# Enabled-Controller.net
KiCad netlist of a schematic drawn in EAGLE
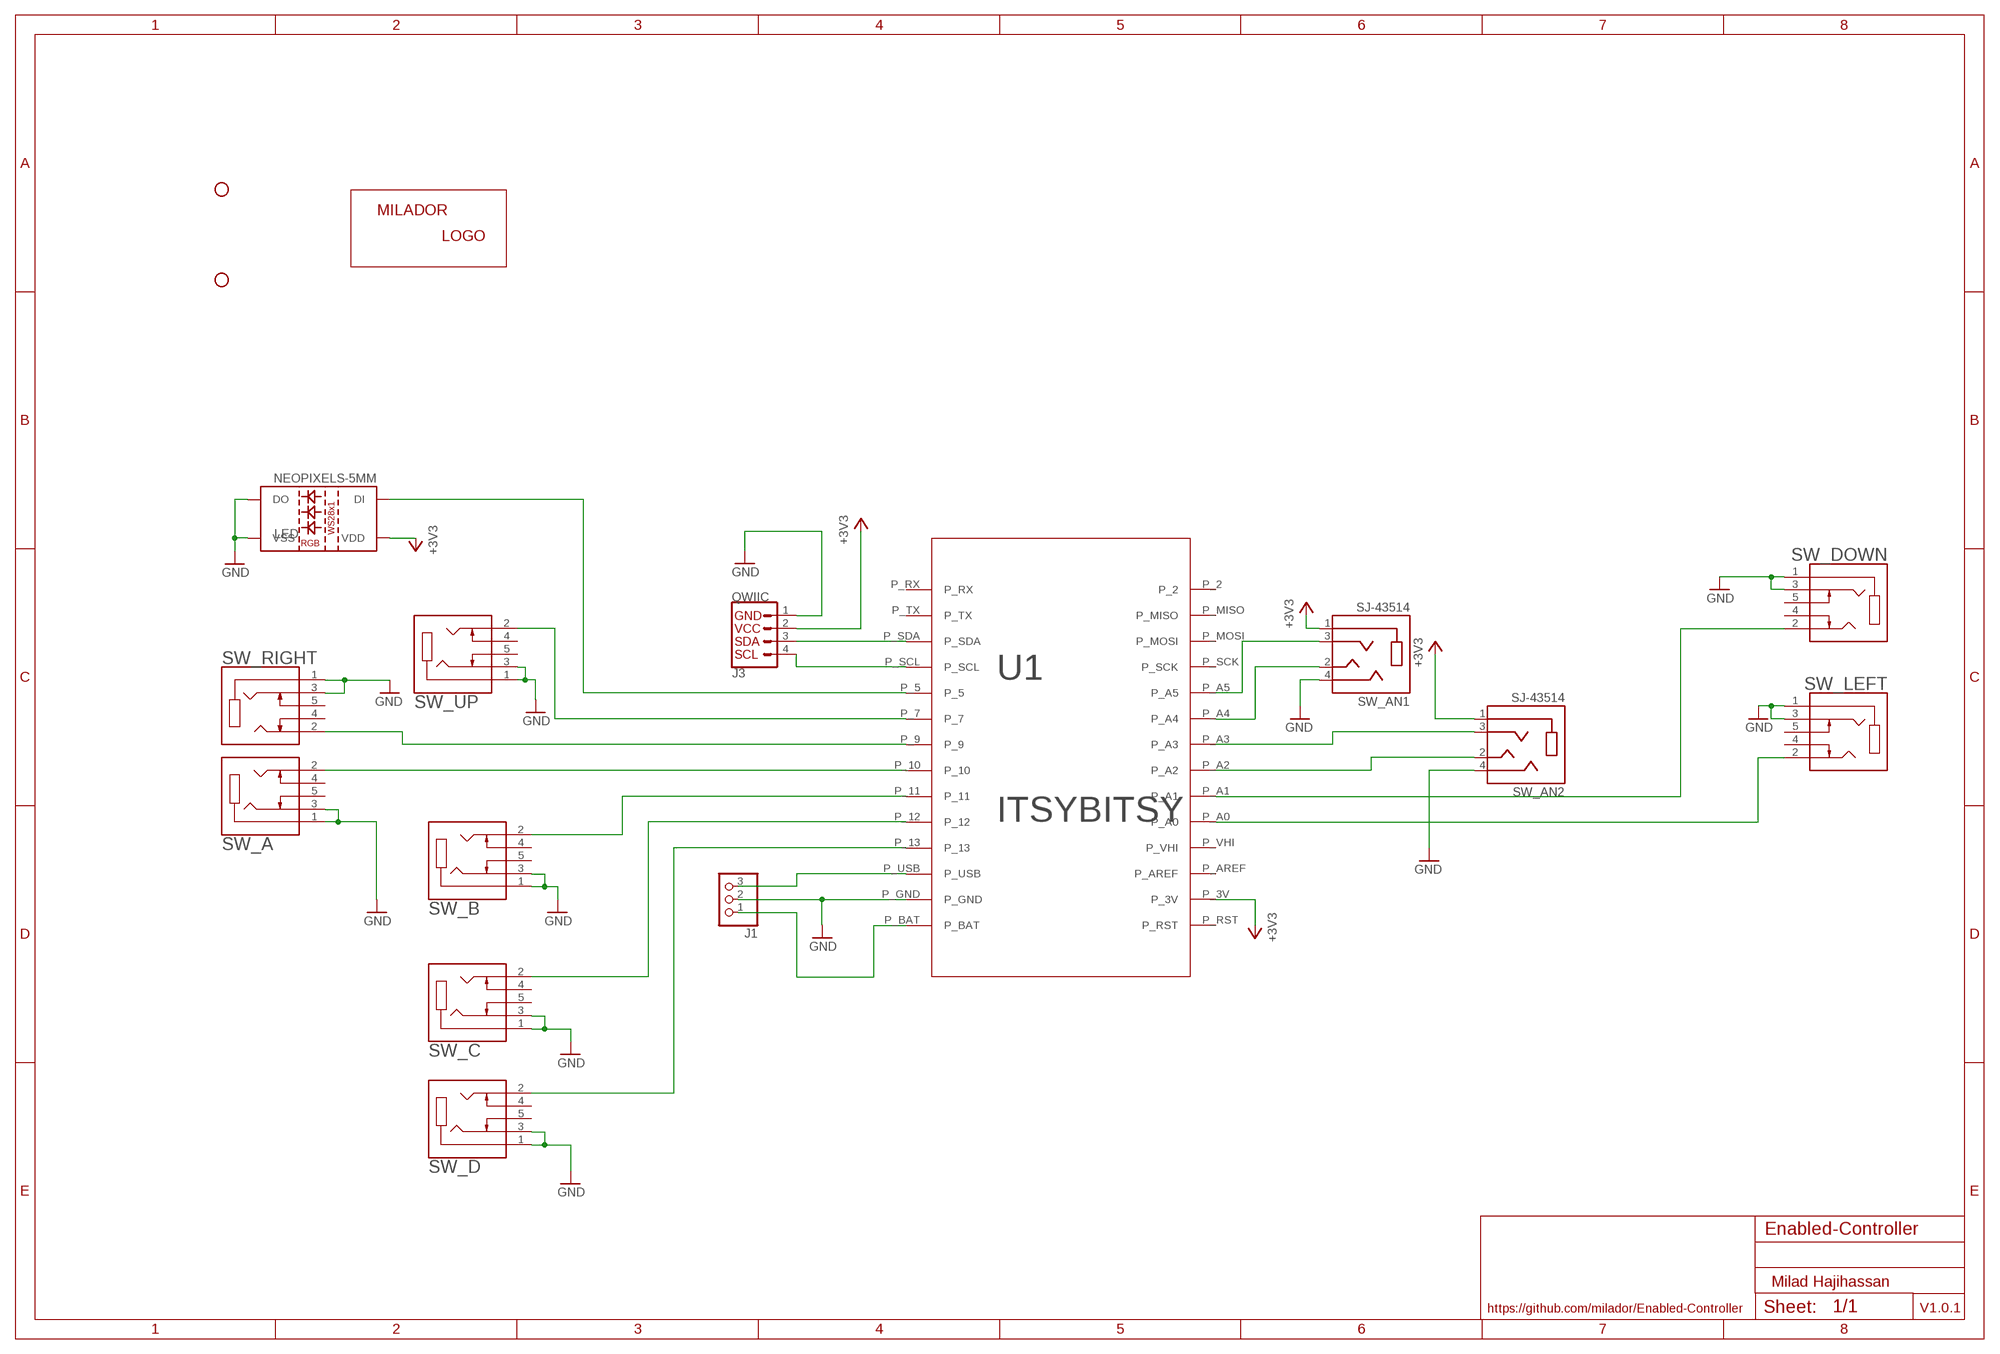
[diagram p0: schematic, sheet 1]

(export (version "E")
  (design (tool "Eeschema 10.0.6"))
  (components
    (comp (ref "J1")
      (value "HEADER_FEMALE-1X3-LONGER")
      (footprint "eagle-import:HEADER_FEMALE-1X03_LONGER")
      (libsource (lib "eagle-import") (part "HEADER_FEMALE-1X3-LONGER"))
    )
    (comp (ref "J3")
      (value "QWIIC")
      (footprint "eagle-import:CONNECTORS_JST04_1MM_RA")
      (libsource (lib "eagle-import") (part "QWIIC_CONNECTORSJS-1MM"))
    )
    (comp (ref "LABEL1")
      (value "MILADOR-LOGO-")
      (footprint "eagle-import:MILADOR_LOGO1")
      (libsource (lib "eagle-import") (part "MILADOR-LOGO-"))
    )
    (comp (ref "LED")
      (value "NEOPIXELS-5MM")
      (footprint "eagle-import:NEOPIXELS-5MM")
      (libsource (lib "eagle-import") (part "NEOPIXELS-5MM"))
    )
    (comp (ref "STANDOFF1")
      (value "STAND-OFF-")
      (footprint "eagle-import:STAND-OFF")
      (libsource (lib "eagle-import") (part "STAND-OFF-"))
    )
    (comp (ref "STANDOFF2")
      (value "STAND-OFF-")
      (footprint "eagle-import:STAND-OFF")
      (libsource (lib "eagle-import") (part "STAND-OFF-"))
    )
    (comp (ref "SW_A")
      (value "CUI_SJ1-3535NGSJ1-3535NG")
      (footprint "eagle-import:CUI_SJ1-3535NG")
      (libsource (lib "eagle-import") (part "CUI_SJ1-3535NGSJ1-3535NG"))
    )
    (comp (ref "SW_AN1")
      (value "SJ-43514")
      (footprint "eagle-import:CUI_SJ-43514")
      (libsource (lib "eagle-import") (part "SJ-43514"))
    )
    (comp (ref "SW_AN2")
      (value "SJ-43514")
      (footprint "eagle-import:CUI_SJ-43514")
      (libsource (lib "eagle-import") (part "SJ-43514"))
    )
    (comp (ref "SW_B")
      (value "CUI_SJ1-3535NGSJ1-3535NG")
      (footprint "eagle-import:CUI_SJ1-3535NG")
      (libsource (lib "eagle-import") (part "CUI_SJ1-3535NGSJ1-3535NG"))
    )
    (comp (ref "SW_C")
      (value "CUI_SJ1-3535NGSJ1-3535NG")
      (footprint "eagle-import:CUI_SJ1-3535NG")
      (libsource (lib "eagle-import") (part "CUI_SJ1-3535NGSJ1-3535NG"))
    )
    (comp (ref "SW_D")
      (value "CUI_SJ1-3535NGSJ1-3535NG")
      (footprint "eagle-import:CUI_SJ1-3535NG")
      (libsource (lib "eagle-import") (part "CUI_SJ1-3535NGSJ1-3535NG"))
    )
    (comp (ref "SW_DOWN")
      (value "CUI_SJ1-3535NGSJ1-3535NG")
      (footprint "eagle-import:CUI_SJ1-3535NG")
      (libsource (lib "eagle-import") (part "CUI_SJ1-3535NGSJ1-3535NG"))
    )
    (comp (ref "SW_LEFT")
      (value "CUI_SJ1-3535NGSJ1-3535NG")
      (footprint "eagle-import:CUI_SJ1-3535NG")
      (libsource (lib "eagle-import") (part "CUI_SJ1-3535NGSJ1-3535NG"))
    )
    (comp (ref "SW_RIGHT")
      (value "CUI_SJ1-3535NGSJ1-3535NG")
      (footprint "eagle-import:CUI_SJ1-3535NG")
      (libsource (lib "eagle-import") (part "CUI_SJ1-3535NGSJ1-3535NG"))
    )
    (comp (ref "SW_UP")
      (value "CUI_SJ1-3535NGSJ1-3535NG")
      (footprint "eagle-import:CUI_SJ1-3535NG")
      (libsource (lib "eagle-import") (part "CUI_SJ1-3535NGSJ1-3535NG"))
    )
    (comp (ref "U1")
      (value "ITSYBITSY")
      (footprint "eagle-import:ITSYBITSY-V2")
      (libsource (lib "eagle-import") (part "ITSYBITSY-V2"))
    )
  )
  (nets
    (net (code "1") (name "+3V3") (class "Default")
      (node (ref "J3") (pin "2") (pinfunction "2_2") (pintype "power_in"))
      (node (ref "LED") (pin "P2") (pinfunction "VDD_P2") (pintype "bidirectional"))
      (node (ref "SW_AN1") (pin "1") (pinfunction "SLEEVE_1") (pintype "passive"))
      (node (ref "SW_AN2") (pin "1") (pinfunction "SLEEVE_1") (pintype "passive"))
      (node (ref "U1") (pin "P_3V") (pinfunction "P_3V_P_3V") (pintype "bidirectional"))
    )
    (net (code "2") (name "GND") (class "Default")
      (node (ref "J1") (pin "2") (pinfunction "2_2") (pintype "passive"))
      (node (ref "J3") (pin "1") (pinfunction "1_1") (pintype "power_in"))
      (node (ref "LED") (pin "P3") (pinfunction "VSS_P3") (pintype "bidirectional"))
      (node (ref "LED") (pin "P4") (pinfunction "DO_P4") (pintype "bidirectional"))
      (node (ref "SW_A") (pin "1") (pinfunction "1_1") (pintype "passive"))
      (node (ref "SW_A") (pin "3") (pinfunction "3_3") (pintype "passive"))
      (node (ref "SW_AN1") (pin "4") (pinfunction "RING2_4") (pintype "passive"))
      (node (ref "SW_AN2") (pin "4") (pinfunction "RING2_4") (pintype "passive"))
      (node (ref "SW_B") (pin "1") (pinfunction "1_1") (pintype "passive"))
      (node (ref "SW_B") (pin "3") (pinfunction "3_3") (pintype "passive"))
      (node (ref "SW_C") (pin "1") (pinfunction "1_1") (pintype "passive"))
      (node (ref "SW_C") (pin "3") (pinfunction "3_3") (pintype "passive"))
      (node (ref "SW_D") (pin "1") (pinfunction "1_1") (pintype "passive"))
      (node (ref "SW_D") (pin "3") (pinfunction "3_3") (pintype "passive"))
      (node (ref "SW_DOWN") (pin "1") (pinfunction "1_1") (pintype "passive"))
      (node (ref "SW_DOWN") (pin "3") (pinfunction "3_3") (pintype "passive"))
      (node (ref "SW_LEFT") (pin "1") (pinfunction "1_1") (pintype "passive"))
      (node (ref "SW_LEFT") (pin "3") (pinfunction "3_3") (pintype "passive"))
      (node (ref "SW_RIGHT") (pin "1") (pinfunction "1_1") (pintype "passive"))
      (node (ref "SW_RIGHT") (pin "3") (pinfunction "3_3") (pintype "passive"))
      (node (ref "SW_UP") (pin "1") (pinfunction "1_1") (pintype "passive"))
      (node (ref "SW_UP") (pin "3") (pinfunction "3_3") (pintype "passive"))
      (node (ref "U1") (pin "P_GND") (pinfunction "P_GND_P_GND") (pintype "bidirectional"))
    )
    (net (code "3") (name "Net-(J1-Pad1)") (class "Default")
      (node (ref "J1") (pin "1") (pinfunction "1_1") (pintype "passive"))
      (node (ref "U1") (pin "P_BAT") (pinfunction "P_BAT_P_BAT") (pintype "bidirectional"))
    )
    (net (code "4") (name "Net-(J1-Pad3)") (class "Default")
      (node (ref "J1") (pin "3") (pinfunction "3_3") (pintype "passive"))
      (node (ref "U1") (pin "P_USB") (pinfunction "P_USB_P_USB") (pintype "bidirectional"))
    )
    (net (code "5") (name "Net-(J3-Pad3)") (class "Default")
      (node (ref "J3") (pin "3") (pinfunction "3_3") (pintype "passive"))
      (node (ref "U1") (pin "P_SDA") (pinfunction "P_SDA_P_SDA") (pintype "bidirectional"))
    )
    (net (code "6") (name "Net-(J3-Pad4)") (class "Default")
      (node (ref "J3") (pin "4") (pinfunction "4_4") (pintype "passive"))
      (node (ref "U1") (pin "P_SCL") (pinfunction "P_SCL_P_SCL") (pintype "bidirectional"))
    )
    (net (code "7") (name "Net-(LED-DI)") (class "Default")
      (node (ref "LED") (pin "P1") (pinfunction "DI_P1") (pintype "bidirectional"))
      (node (ref "U1") (pin "P_5") (pinfunction "P_5_P_5") (pintype "bidirectional"))
    )
    (net (code "8") (name "Net-(SW_A-Pad2)") (class "Default")
      (node (ref "SW_A") (pin "2") (pinfunction "2_2") (pintype "passive"))
      (node (ref "U1") (pin "P_10") (pinfunction "P_10_P_10") (pintype "bidirectional"))
    )
    (net (code "9") (name "Net-(SW_AN1-RING1)") (class "Default")
      (node (ref "SW_AN1") (pin "3") (pinfunction "RING1_3") (pintype "passive"))
      (node (ref "U1") (pin "P_A5") (pinfunction "P_A5_P_A5") (pintype "bidirectional"))
    )
    (net (code "10") (name "Net-(SW_AN1-TIP)") (class "Default")
      (node (ref "SW_AN1") (pin "2") (pinfunction "TIP_2") (pintype "passive"))
      (node (ref "U1") (pin "P_A4") (pinfunction "P_A4_P_A4") (pintype "bidirectional"))
    )
    (net (code "11") (name "Net-(SW_AN2-RING1)") (class "Default")
      (node (ref "SW_AN2") (pin "3") (pinfunction "RING1_3") (pintype "passive"))
      (node (ref "U1") (pin "P_A3") (pinfunction "P_A3_P_A3") (pintype "bidirectional"))
    )
    (net (code "12") (name "Net-(SW_AN2-TIP)") (class "Default")
      (node (ref "SW_AN2") (pin "2") (pinfunction "TIP_2") (pintype "passive"))
      (node (ref "U1") (pin "P_A2") (pinfunction "P_A2_P_A2") (pintype "bidirectional"))
    )
    (net (code "13") (name "Net-(SW_B-Pad2)") (class "Default")
      (node (ref "SW_B") (pin "2") (pinfunction "2_2") (pintype "passive"))
      (node (ref "U1") (pin "P_11") (pinfunction "P_11_P_11") (pintype "bidirectional"))
    )
    (net (code "14") (name "Net-(SW_C-Pad2)") (class "Default")
      (node (ref "SW_C") (pin "2") (pinfunction "2_2") (pintype "passive"))
      (node (ref "U1") (pin "P_12") (pinfunction "P_12_P_12") (pintype "bidirectional"))
    )
    (net (code "15") (name "Net-(SW_D-Pad2)") (class "Default")
      (node (ref "SW_D") (pin "2") (pinfunction "2_2") (pintype "passive"))
      (node (ref "U1") (pin "P_13") (pinfunction "P_13_P_13") (pintype "bidirectional"))
    )
    (net (code "16") (name "Net-(SW_DOWN-Pad2)") (class "Default")
      (node (ref "SW_DOWN") (pin "2") (pinfunction "2_2") (pintype "passive"))
      (node (ref "U1") (pin "P_A1") (pinfunction "P_A1_P_A1") (pintype "bidirectional"))
    )
    (net (code "17") (name "Net-(SW_LEFT-Pad2)") (class "Default")
      (node (ref "SW_LEFT") (pin "2") (pinfunction "2_2") (pintype "passive"))
      (node (ref "U1") (pin "P_A0") (pinfunction "P_A0_P_A0") (pintype "bidirectional"))
    )
    (net (code "18") (name "Net-(SW_RIGHT-Pad2)") (class "Default")
      (node (ref "SW_RIGHT") (pin "2") (pinfunction "2_2") (pintype "passive"))
      (node (ref "U1") (pin "P_9") (pinfunction "P_9_P_9") (pintype "bidirectional"))
    )
    (net (code "19") (name "Net-(SW_UP-Pad2)") (class "Default")
      (node (ref "SW_UP") (pin "2") (pinfunction "2_2") (pintype "passive"))
      (node (ref "U1") (pin "P_7") (pinfunction "P_7_P_7") (pintype "bidirectional"))
    )
    (net (code "20") (name "unconnected-(SW_A-Pad4)") (class "Default")
      (node (ref "SW_A") (pin "4") (pinfunction "4_4") (pintype "passive"))
    )
    (net (code "21") (name "unconnected-(SW_A-Pad5)") (class "Default")
      (node (ref "SW_A") (pin "5") (pinfunction "5_5") (pintype "passive"))
    )
    (net (code "22") (name "unconnected-(SW_B-Pad4)") (class "Default")
      (node (ref "SW_B") (pin "4") (pinfunction "4_4") (pintype "passive"))
    )
    (net (code "23") (name "unconnected-(SW_B-Pad5)") (class "Default")
      (node (ref "SW_B") (pin "5") (pinfunction "5_5") (pintype "passive"))
    )
    (net (code "24") (name "unconnected-(SW_C-Pad4)") (class "Default")
      (node (ref "SW_C") (pin "4") (pinfunction "4_4") (pintype "passive"))
    )
    (net (code "25") (name "unconnected-(SW_C-Pad5)") (class "Default")
      (node (ref "SW_C") (pin "5") (pinfunction "5_5") (pintype "passive"))
    )
    (net (code "26") (name "unconnected-(SW_D-Pad4)") (class "Default")
      (node (ref "SW_D") (pin "4") (pinfunction "4_4") (pintype "passive"))
    )
    (net (code "27") (name "unconnected-(SW_D-Pad5)") (class "Default")
      (node (ref "SW_D") (pin "5") (pinfunction "5_5") (pintype "passive"))
    )
    (net (code "28") (name "unconnected-(SW_DOWN-Pad4)") (class "Default")
      (node (ref "SW_DOWN") (pin "4") (pinfunction "4_4") (pintype "passive"))
    )
    (net (code "29") (name "unconnected-(SW_DOWN-Pad5)") (class "Default")
      (node (ref "SW_DOWN") (pin "5") (pinfunction "5_5") (pintype "passive"))
    )
    (net (code "30") (name "unconnected-(SW_LEFT-Pad4)") (class "Default")
      (node (ref "SW_LEFT") (pin "4") (pinfunction "4_4") (pintype "passive"))
    )
    (net (code "31") (name "unconnected-(SW_LEFT-Pad5)") (class "Default")
      (node (ref "SW_LEFT") (pin "5") (pinfunction "5_5") (pintype "passive"))
    )
    (net (code "32") (name "unconnected-(SW_RIGHT-Pad4)") (class "Default")
      (node (ref "SW_RIGHT") (pin "4") (pinfunction "4_4") (pintype "passive"))
    )
    (net (code "33") (name "unconnected-(SW_RIGHT-Pad5)") (class "Default")
      (node (ref "SW_RIGHT") (pin "5") (pinfunction "5_5") (pintype "passive"))
    )
    (net (code "34") (name "unconnected-(SW_UP-Pad4)") (class "Default")
      (node (ref "SW_UP") (pin "4") (pinfunction "4_4") (pintype "passive"))
    )
    (net (code "35") (name "unconnected-(SW_UP-Pad5)") (class "Default")
      (node (ref "SW_UP") (pin "5") (pinfunction "5_5") (pintype "passive"))
    )
    (net (code "36") (name "unconnected-(U1-PadP_2)") (class "Default")
      (node (ref "U1") (pin "P_2") (pinfunction "P_2_P_2") (pintype "bidirectional"))
    )
    (net (code "37") (name "unconnected-(U1-PadP_AREF)") (class "Default")
      (node (ref "U1") (pin "P_AREF") (pinfunction "P_AREF_P_AREF") (pintype "bidirectional"))
    )
    (net (code "38") (name "unconnected-(U1-PadP_MISO)") (class "Default")
      (node (ref "U1") (pin "P_MISO") (pinfunction "P_MISO_P_MISO") (pintype "bidirectional"))
    )
    (net (code "39") (name "unconnected-(U1-PadP_MOSI)") (class "Default")
      (node (ref "U1") (pin "P_MOSI") (pinfunction "P_MOSI_P_MOSI") (pintype "bidirectional"))
    )
    (net (code "40") (name "unconnected-(U1-PadP_RST)") (class "Default")
      (node (ref "U1") (pin "P_RST") (pinfunction "P_RST_P_RST") (pintype "bidirectional"))
    )
    (net (code "41") (name "unconnected-(U1-PadP_RX)") (class "Default")
      (node (ref "U1") (pin "P_RX") (pinfunction "P_RX_P_RX") (pintype "bidirectional"))
    )
    (net (code "42") (name "unconnected-(U1-PadP_SCK)") (class "Default")
      (node (ref "U1") (pin "P_SCK") (pinfunction "P_SCK_P_SCK") (pintype "bidirectional"))
    )
    (net (code "43") (name "unconnected-(U1-PadP_TX)") (class "Default")
      (node (ref "U1") (pin "P_TX") (pinfunction "P_TX_P_TX") (pintype "bidirectional"))
    )
    (net (code "44") (name "unconnected-(U1-PadP_VHI)") (class "Default")
      (node (ref "U1") (pin "P_VHI") (pinfunction "P_VHI_P_VHI") (pintype "bidirectional"))
    )
  )
)
